# BlockDiagram.net
KiCad netlist of a schematic drawn in Altium Designer
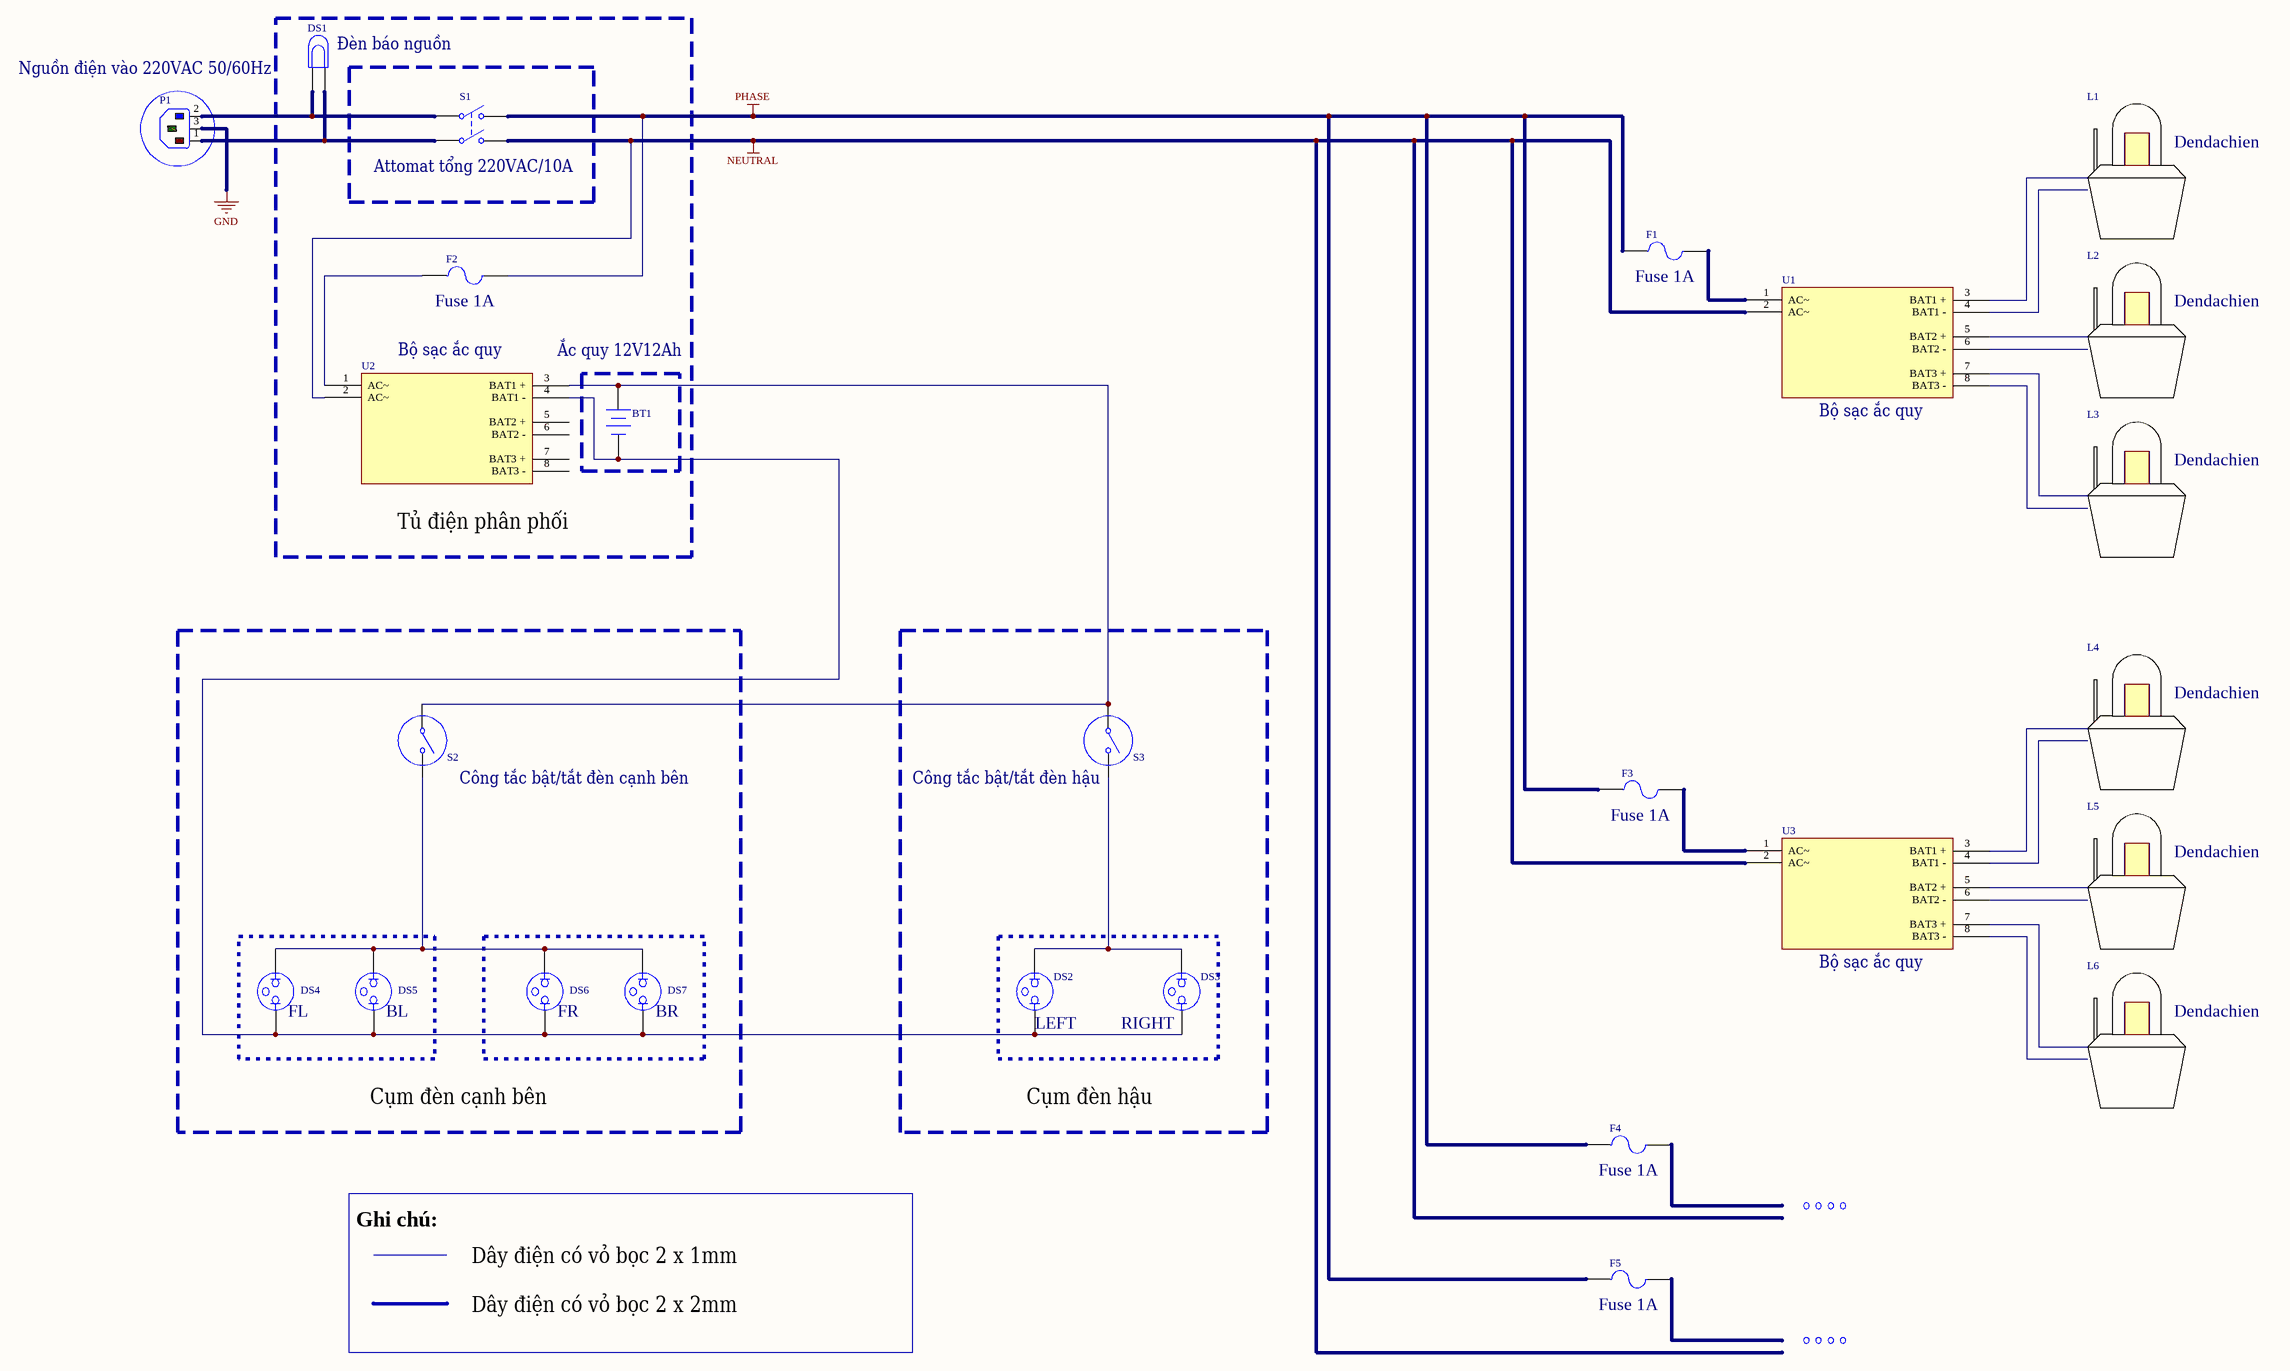
[diagram p0: BlockDiagram.SchDoc]

(export (version "E")
  (design (tool "Eeschema 10.0.6"))
  (components
    (comp (ref "BT1")
      (value "Ắc quy 12V12Ah")
      (footprint "BAT-2")
      (description "Multicell Battery")
      (fields (field (name "PUBLISHER") "Altium Limited"))
      (libsource (lib "Miscellaneous Devices") (part "Battery"))
    )
    (comp (ref "DS1")
      (value "Đèn báo nguồn")
      (footprint "PIN2")
      (description "Incandescent Bulb")
      (fields (field (name "PUBLISHER") "Altium Limited"))
      (libsource (lib "Miscellaneous Devices") (part "Lamp"))
    )
    (comp (ref "DS2")
      (value "LEFT")
      (footprint "PIN2")
      (description "Neon Lamp")
      (fields (field (name "PUBLISHER") "Altium Limited"))
      (libsource (lib "Miscellaneous Devices") (part "Lamp Neon"))
    )
    (comp (ref "DS3")
      (value "RIGHT")
      (footprint "PIN2")
      (description "Neon Lamp")
      (fields (field (name "PUBLISHER") "Altium Limited"))
      (libsource (lib "Miscellaneous Devices") (part "Lamp Neon"))
    )
    (comp (ref "DS4")
      (value "FL")
      (footprint "PIN2")
      (description "Neon Lamp")
      (fields (field (name "PUBLISHER") "Altium Limited"))
      (libsource (lib "Miscellaneous Devices") (part "Lamp Neon"))
    )
    (comp (ref "DS5")
      (value "BL")
      (footprint "PIN2")
      (description "Neon Lamp")
      (fields (field (name "PUBLISHER") "Altium Limited"))
      (libsource (lib "Miscellaneous Devices") (part "Lamp Neon"))
    )
    (comp (ref "DS6")
      (value "FR")
      (footprint "PIN2")
      (description "Neon Lamp")
      (fields (field (name "PUBLISHER") "Altium Limited"))
      (libsource (lib "Miscellaneous Devices") (part "Lamp Neon"))
    )
    (comp (ref "DS7")
      (value "BR")
      (footprint "PIN2")
      (description "Neon Lamp")
      (fields (field (name "PUBLISHER") "Altium Limited"))
      (libsource (lib "Miscellaneous Devices") (part "Lamp Neon"))
    )
    (comp (ref "F1")
      (value "Fuse 1A")
      (footprint "PIN-W2/E2.8")
      (description "Fuse")
      (fields (field (name "PUBLISHER") "Altium Limited"))
      (libsource (lib "Miscellaneous Devices") (part "Fuse 2"))
    )
    (comp (ref "F2")
      (value "Fuse 1A")
      (footprint "PIN-W2/E2.8")
      (description "Fuse")
      (fields (field (name "PUBLISHER") "Altium Limited"))
      (libsource (lib "Miscellaneous Devices") (part "Fuse 2"))
    )
    (comp (ref "F3")
      (value "Fuse 1A")
      (footprint "PIN-W2/E2.8")
      (description "Fuse")
      (fields (field (name "PUBLISHER") "Altium Limited"))
      (libsource (lib "Miscellaneous Devices") (part "Fuse 2"))
    )
    (comp (ref "F4")
      (value "Fuse 1A")
      (footprint "PIN-W2/E2.8")
      (description "Fuse")
      (fields (field (name "PUBLISHER") "Altium Limited"))
      (libsource (lib "Miscellaneous Devices") (part "Fuse 2"))
    )
    (comp (ref "F5")
      (value "Fuse 1A")
      (footprint "PIN-W2/E2.8")
      (description "Fuse")
      (fields (field (name "PUBLISHER") "Altium Limited"))
      (libsource (lib "Miscellaneous Devices") (part "Fuse 2"))
    )
    (comp (ref "L1") (value "Dendachien") (libsource (lib "DnsSchLib") (part "Dendachien")))
    (comp (ref "L2") (value "Dendachien") (libsource (lib "DnsSchLib") (part "Dendachien")))
    (comp (ref "L3") (value "Dendachien") (libsource (lib "DnsSchLib") (part "Dendachien")))
    (comp (ref "L4") (value "Dendachien") (libsource (lib "DnsSchLib") (part "Dendachien")))
    (comp (ref "L5") (value "Dendachien") (libsource (lib "DnsSchLib") (part "Dendachien")))
    (comp (ref "L6") (value "Dendachien") (libsource (lib "DnsSchLib") (part "Dendachien")))
    (comp (ref "P1")
      (value "Nguồn điện vào 220VAC 50/60Hz")
      (footprint "IEC9.14-2H3")
      (description "IEC Mains Power Inlet, EN60 320-1 C14 Class I Cold Condition, PC Flange Rear Mount, Chassis Plug")
      (fields (field (name "PUBLISHER") "Altium Limited"))
      (libsource (lib "Miscellaneous Connectors") (part "Plug AC Male"))
    )
    (comp (ref "S1")
      (value "Attomat tổng 220VAC/10A")
      (footprint "DPST-4")
      (description "Double-Pole, Single-Throw Switch")
      (fields (field (name "PUBLISHER") "Altium Limited"))
      (libsource (lib "Miscellaneous Devices") (part "SW-DPST"))
    )
    (comp (ref "S2")
      (value "Công tắc bật/tắt đèn cạnh bên")
      (footprint "SPST-2")
      (description "Single-Pole, Single-Throw Switch")
      (fields (field (name "PUBLISHER") "Altium Limited"))
      (libsource (lib "Miscellaneous Devices") (part "SW-SPST"))
    )
    (comp (ref "S3")
      (value "Công tắc bật/tắt đèn hậu")
      (footprint "SPST-2")
      (description "Single-Pole, Single-Throw Switch")
      (fields (field (name "PUBLISHER") "Altium Limited"))
      (libsource (lib "Miscellaneous Devices") (part "SW-SPST"))
    )
    (comp (ref "U1") (value "Bộ sạc ắc quy") (libsource (lib "DnsSchLib") (part "Bosacacquy")))
    (comp (ref "U2") (value "Bộ sạc ắc quy") (libsource (lib "DnsSchLib") (part "Bosacacquy")))
    (comp (ref "U3") (value "Bộ sạc ắc quy") (libsource (lib "DnsSchLib") (part "Bosacacquy")))
  )
  (nets
    (net (code "1") (name "GND") (class "Default")
      (node (ref "P1") (pin "3") (pinfunction "E_3") (pintype "power_in"))
    )
    (net (code "2") (name "NEUTRAL") (class "Default")
      (node (ref "S1") (pin "4") (pinfunction "NO2_4") (pintype "passive"))
      (node (ref "U1") (pin "2") (pinfunction "AC~_2") (pintype "passive"))
      (node (ref "U2") (pin "2") (pinfunction "AC~_2") (pintype "passive"))
      (node (ref "U3") (pin "2") (pinfunction "AC~_2") (pintype "passive"))
    )
    (net (code "3") (name "Net-(BT1-+)") (class "Default")
      (node (ref "BT1") (pin "1") (pinfunction "+_1") (pintype "passive"))
      (node (ref "S2") (pin "1") (pinfunction "COMMON_1") (pintype "passive"))
      (node (ref "S3") (pin "1") (pinfunction "COMMON_1") (pintype "passive"))
      (node (ref "U2") (pin "3") (pinfunction "BAT1_+_3") (pintype "passive"))
    )
    (net (code "4") (name "Net-(BT1--)") (class "Default")
      (node (ref "BT1") (pin "2") (pinfunction "-_2") (pintype "passive"))
      (node (ref "DS2") (pin "1") (pinfunction "1_1") (pintype "passive"))
      (node (ref "DS3") (pin "1") (pinfunction "1_1") (pintype "passive"))
      (node (ref "DS4") (pin "1") (pinfunction "1_1") (pintype "passive"))
      (node (ref "DS5") (pin "1") (pinfunction "1_1") (pintype "passive"))
      (node (ref "DS6") (pin "1") (pinfunction "1_1") (pintype "passive"))
      (node (ref "DS7") (pin "1") (pinfunction "1_1") (pintype "passive"))
      (node (ref "U2") (pin "4") (pinfunction "BAT1_-_4") (pintype "passive"))
    )
    (net (code "5") (name "Net-(F1-Pad2)") (class "Default")
      (node (ref "F1") (pin "2") (pinfunction "2_2") (pintype "passive"))
      (node (ref "U1") (pin "1") (pinfunction "AC~_1") (pintype "passive"))
    )
    (net (code "6") (name "Net-(F2-Pad1)") (class "Default")
      (node (ref "F2") (pin "1") (pinfunction "1_1") (pintype "passive"))
      (node (ref "U2") (pin "1") (pinfunction "AC~_1") (pintype "passive"))
    )
    (net (code "7") (name "Net-(F3-Pad2)") (class "Default")
      (node (ref "F3") (pin "2") (pinfunction "2_2") (pintype "passive"))
      (node (ref "U3") (pin "1") (pinfunction "AC~_1") (pintype "passive"))
    )
    (net (code "8") (name "Net-(P1-L)") (class "Default")
      (node (ref "DS1") (pin "2") (pinfunction "2_2") (pintype "passive"))
      (node (ref "P1") (pin "1") (pinfunction "L_1") (pintype "power_in"))
      (node (ref "S1") (pin "3") (pinfunction "COMMON2_3") (pintype "passive"))
    )
    (net (code "9") (name "Net-(P1-N)") (class "Default")
      (node (ref "DS1") (pin "1") (pinfunction "1_1") (pintype "passive"))
      (node (ref "P1") (pin "2") (pinfunction "N_2") (pintype "power_in"))
      (node (ref "S1") (pin "1") (pinfunction "COMMON1_1") (pintype "passive"))
    )
    (net (code "10") (name "Net-(S2-NO)") (class "Default")
      (node (ref "DS4") (pin "2") (pinfunction "2_2") (pintype "passive"))
      (node (ref "DS5") (pin "2") (pinfunction "2_2") (pintype "passive"))
      (node (ref "DS6") (pin "2") (pinfunction "2_2") (pintype "passive"))
      (node (ref "DS7") (pin "2") (pinfunction "2_2") (pintype "passive"))
      (node (ref "S2") (pin "2") (pinfunction "NO_2") (pintype "passive"))
    )
    (net (code "11") (name "Net-(S3-NO)") (class "Default")
      (node (ref "DS2") (pin "2") (pinfunction "2_2") (pintype "passive"))
      (node (ref "DS3") (pin "2") (pinfunction "2_2") (pintype "passive"))
      (node (ref "S3") (pin "2") (pinfunction "NO_2") (pintype "passive"))
    )
    (net (code "12") (name "PHASE") (class "Default")
      (node (ref "F1") (pin "1") (pinfunction "1_1") (pintype "passive"))
      (node (ref "F2") (pin "2") (pinfunction "2_2") (pintype "passive"))
      (node (ref "F3") (pin "1") (pinfunction "1_1") (pintype "passive"))
      (node (ref "F4") (pin "1") (pinfunction "1_1") (pintype "passive"))
      (node (ref "F5") (pin "1") (pinfunction "1_1") (pintype "passive"))
      (node (ref "S1") (pin "2") (pinfunction "NO1_2") (pintype "passive"))
    )
    (net (code "13") (name "unconnected-(F4-Pad2)") (class "Default")
      (node (ref "F4") (pin "2") (pinfunction "2_2") (pintype "passive"))
    )
    (net (code "14") (name "unconnected-(F5-Pad2)") (class "Default")
      (node (ref "F5") (pin "2") (pinfunction "2_2") (pintype "passive"))
    )
    (net (code "15") (name "unconnected-(U1-BAT1_+-Pad3)") (class "Default")
      (node (ref "U1") (pin "3") (pinfunction "BAT1_+_3") (pintype "passive"))
    )
    (net (code "16") (name "unconnected-(U1-BAT1_--Pad4)") (class "Default")
      (node (ref "U1") (pin "4") (pinfunction "BAT1_-_4") (pintype "passive"))
    )
    (net (code "17") (name "unconnected-(U1-BAT2_+-Pad5)") (class "Default")
      (node (ref "U1") (pin "5") (pinfunction "BAT2_+_5") (pintype "passive"))
    )
    (net (code "18") (name "unconnected-(U1-BAT2_--Pad6)") (class "Default")
      (node (ref "U1") (pin "6") (pinfunction "BAT2_-_6") (pintype "passive"))
    )
    (net (code "19") (name "unconnected-(U1-BAT3_+-Pad7)") (class "Default")
      (node (ref "U1") (pin "7") (pinfunction "BAT3_+_7") (pintype "passive"))
    )
    (net (code "20") (name "unconnected-(U1-BAT3_--Pad8)") (class "Default")
      (node (ref "U1") (pin "8") (pinfunction "BAT3_-_8") (pintype "passive"))
    )
    (net (code "21") (name "unconnected-(U2-BAT2_+-Pad5)") (class "Default")
      (node (ref "U2") (pin "5") (pinfunction "BAT2_+_5") (pintype "passive"))
    )
    (net (code "22") (name "unconnected-(U2-BAT2_--Pad6)") (class "Default")
      (node (ref "U2") (pin "6") (pinfunction "BAT2_-_6") (pintype "passive"))
    )
    (net (code "23") (name "unconnected-(U2-BAT3_+-Pad7)") (class "Default")
      (node (ref "U2") (pin "7") (pinfunction "BAT3_+_7") (pintype "passive"))
    )
    (net (code "24") (name "unconnected-(U2-BAT3_--Pad8)") (class "Default")
      (node (ref "U2") (pin "8") (pinfunction "BAT3_-_8") (pintype "passive"))
    )
    (net (code "25") (name "unconnected-(U3-BAT1_+-Pad3)") (class "Default")
      (node (ref "U3") (pin "3") (pinfunction "BAT1_+_3") (pintype "passive"))
    )
    (net (code "26") (name "unconnected-(U3-BAT1_--Pad4)") (class "Default")
      (node (ref "U3") (pin "4") (pinfunction "BAT1_-_4") (pintype "passive"))
    )
    (net (code "27") (name "unconnected-(U3-BAT2_+-Pad5)") (class "Default")
      (node (ref "U3") (pin "5") (pinfunction "BAT2_+_5") (pintype "passive"))
    )
    (net (code "28") (name "unconnected-(U3-BAT2_--Pad6)") (class "Default")
      (node (ref "U3") (pin "6") (pinfunction "BAT2_-_6") (pintype "passive"))
    )
    (net (code "29") (name "unconnected-(U3-BAT3_+-Pad7)") (class "Default")
      (node (ref "U3") (pin "7") (pinfunction "BAT3_+_7") (pintype "passive"))
    )
    (net (code "30") (name "unconnected-(U3-BAT3_--Pad8)") (class "Default")
      (node (ref "U3") (pin "8") (pinfunction "BAT3_-_8") (pintype "passive"))
    )
  )
)
